# wiring_bord-old.net
KiCad netlist of a schematic drawn in EAGLE
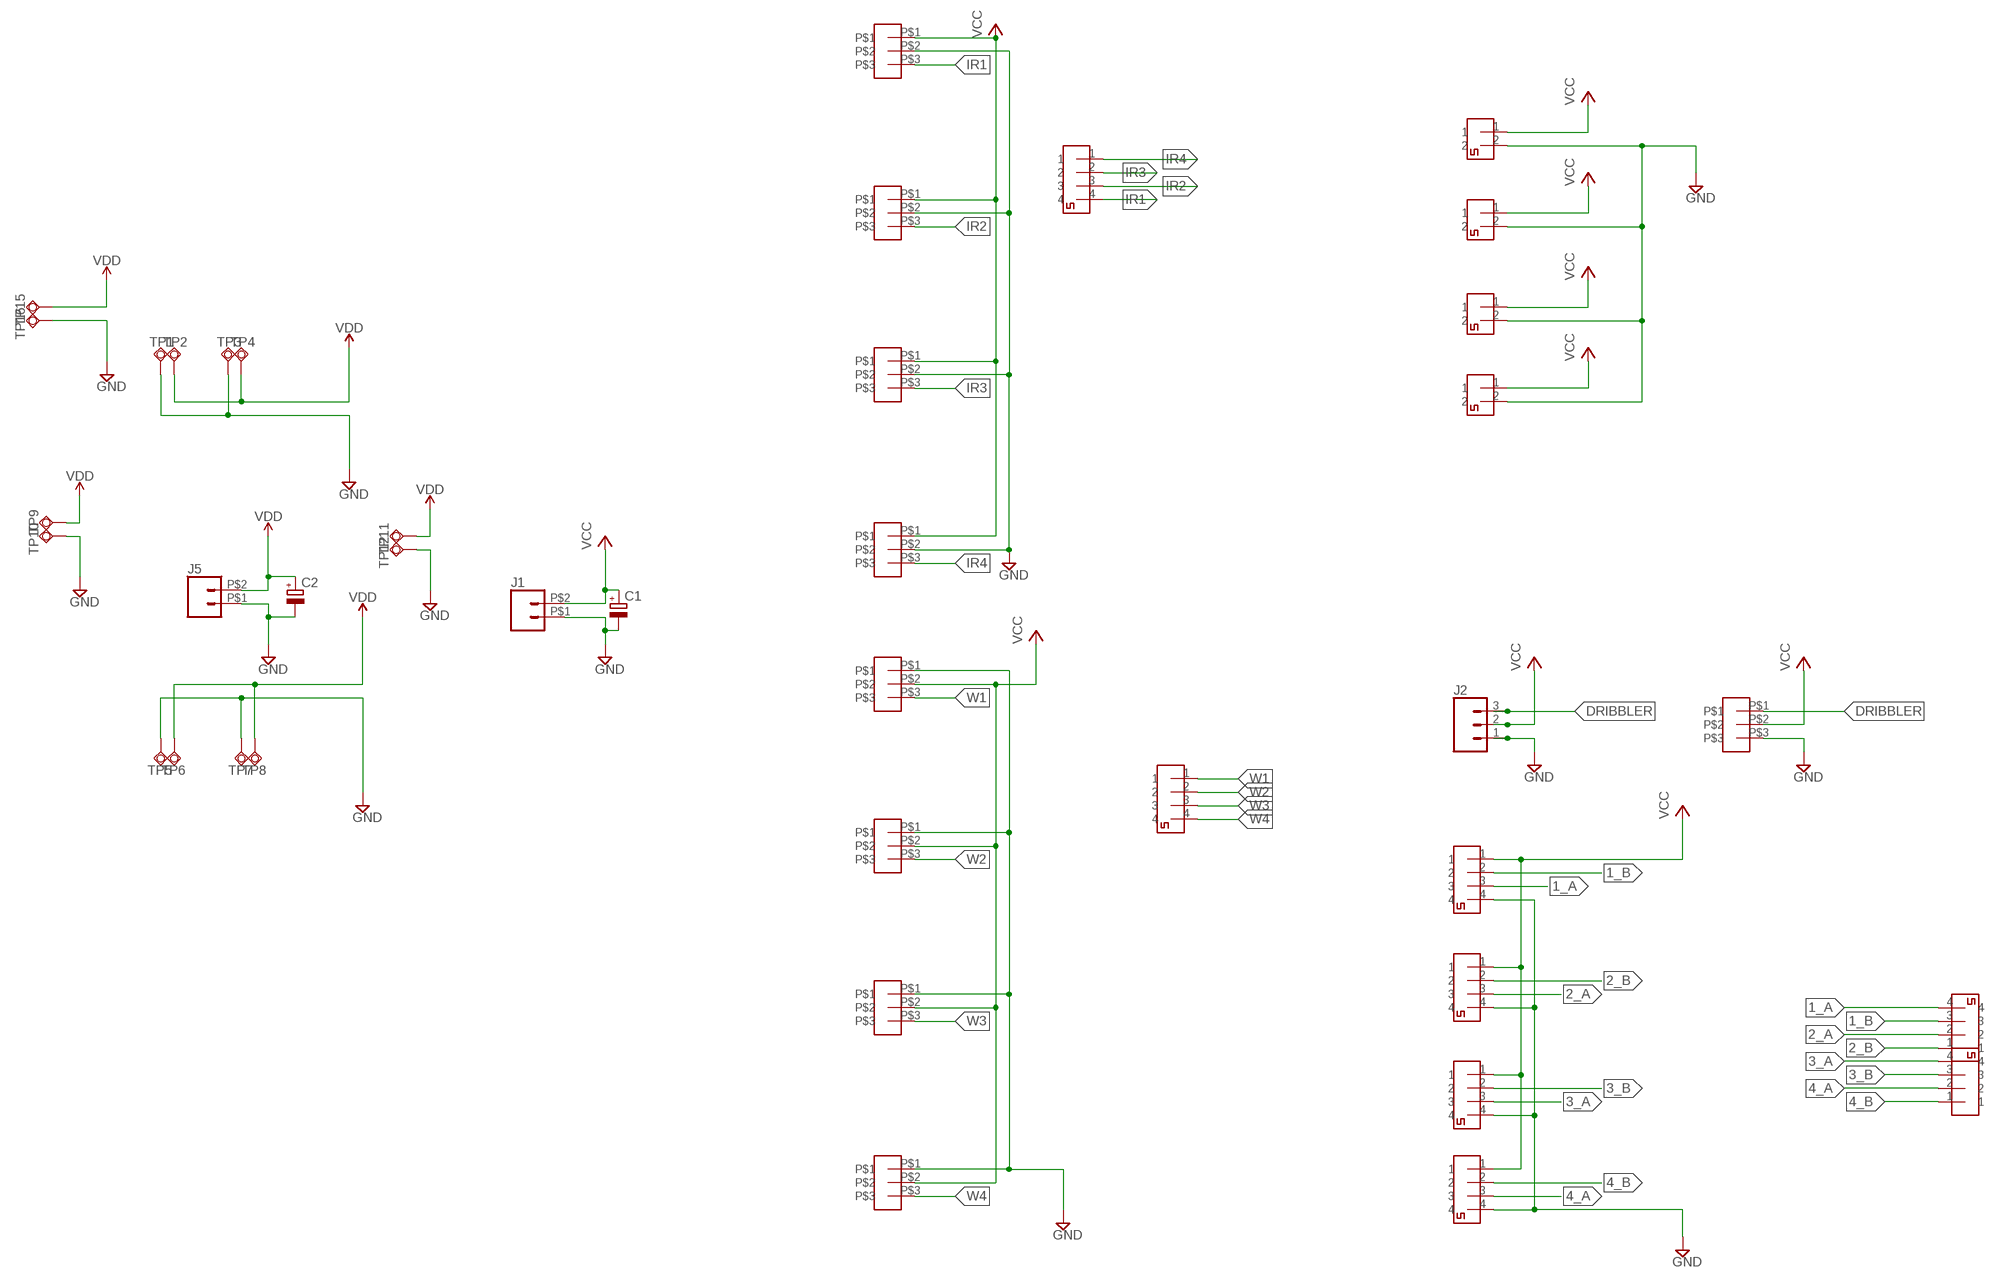
[diagram p0: schematic, sheet 1]

(export (version "E")
  (design (tool "Eeschema 10.0.6"))
  (components
    (comp (ref "C1")
      (value "CPOL-EUE2-5")
      (footprint "eagle-import:E2-5")
      (libsource (lib "eagle-import") (part "CPOL-EUE2-5"))
    )
    (comp (ref "C2")
      (value "CPOL-EUE2-5")
      (footprint "eagle-import:E2-5")
      (libsource (lib "eagle-import") (part "CPOL-EUE2-5"))
    )
    (comp (ref "CONNECTOR1")
      (value "2PIN")
      (footprint "eagle-import:2PIN")
      (libsource (lib "eagle-import") (part "4pin_small_2PIN"))
    )
    (comp (ref "CONNECTOR2")
      (value "2PIN")
      (footprint "eagle-import:2PIN")
      (libsource (lib "eagle-import") (part "4pin_small_2PIN"))
    )
    (comp (ref "CONNECTOR3")
      (value "2PIN")
      (footprint "eagle-import:2PIN")
      (libsource (lib "eagle-import") (part "4pin_small_2PIN"))
    )
    (comp (ref "CONNECTOR4")
      (value "2PIN")
      (footprint "eagle-import:2PIN")
      (libsource (lib "eagle-import") (part "4pin_small_2PIN"))
    )
    (comp (ref "CONNECTOR5")
      (value "2PIN")
      (footprint "eagle-import:2PIN")
      (libsource (lib "eagle-import") (part "2PIN"))
    )
    (comp (ref "CONNECTOR6")
      (value "2PIN")
      (footprint "eagle-import:2PIN")
      (libsource (lib "eagle-import") (part "2PIN"))
    )
    (comp (ref "CONNECTOR7")
      (value "2PIN")
      (footprint "eagle-import:2PIN")
      (libsource (lib "eagle-import") (part "2PIN"))
    )
    (comp (ref "CONNECTOR8")
      (value "2PIN")
      (footprint "eagle-import:2PIN")
      (libsource (lib "eagle-import") (part "2PIN"))
    )
    (comp (ref "ENCODER1")
      (value "2PIN")
      (footprint "eagle-import:2PIN")
      (libsource (lib "eagle-import") (part "4pin_small_2PIN"))
    )
    (comp (ref "ENCODER2")
      (value "2PIN")
      (footprint "eagle-import:2PIN")
      (libsource (lib "eagle-import") (part "4pin_small_2PIN"))
    )
    (comp (ref "ENCODER3")
      (value "2PIN")
      (footprint "eagle-import:2PIN")
      (libsource (lib "eagle-import") (part "4pin_small_2PIN"))
    )
    (comp (ref "ENCODER4")
      (value "2PIN")
      (footprint "eagle-import:2PIN")
      (libsource (lib "eagle-import") (part "4pin_small_2PIN"))
    )
    (comp (ref "IR_DISTANCE1")
      (value "3PIN")
      (footprint "eagle-import:3PIN")
      (libsource (lib "eagle-import") (part "3PIN"))
    )
    (comp (ref "IR_DISTANCE2")
      (value "3PIN")
      (footprint "eagle-import:3PIN")
      (libsource (lib "eagle-import") (part "3PIN"))
    )
    (comp (ref "IR_DISTANCE3")
      (value "3PIN")
      (footprint "eagle-import:3PIN")
      (libsource (lib "eagle-import") (part "3PIN"))
    )
    (comp (ref "IR_DISTANCE4")
      (value "3PIN")
      (footprint "eagle-import:3PIN")
      (libsource (lib "eagle-import") (part "3PIN"))
    )
    (comp (ref "J1")
      (value "CONN_02PTH2")
      (footprint "eagle-import:1X02_BIG")
      (libsource (lib "eagle-import") (part "CONN_02PTH2"))
    )
    (comp (ref "J2")
      (value "CONN_03")
      (footprint "eagle-import:1X03")
      (libsource (lib "eagle-import") (part "CONN_03"))
    )
    (comp (ref "J5")
      (value "CONN_02PTH2")
      (footprint "eagle-import:1X02_BIG")
      (libsource (lib "eagle-import") (part "CONN_02PTH2"))
    )
    (comp (ref "TP1")
      (value "TESTPAD_TPSQPAD1-20")
      (footprint "eagle-import:TESTPAD_P1-20")
      (libsource (lib "eagle-import") (part "TESTPAD_TPSQPAD1-20"))
    )
    (comp (ref "TP2")
      (value "TESTPAD_TPSQPAD1-20")
      (footprint "eagle-import:TESTPAD_P1-20")
      (libsource (lib "eagle-import") (part "TESTPAD_TPSQPAD1-20"))
    )
    (comp (ref "TP3")
      (value "TESTPAD_TPSQPAD1-20")
      (footprint "eagle-import:TESTPAD_P1-20")
      (libsource (lib "eagle-import") (part "TESTPAD_TPSQPAD1-20"))
    )
    (comp (ref "TP4")
      (value "TESTPAD_TPSQPAD1-20")
      (footprint "eagle-import:TESTPAD_P1-20")
      (libsource (lib "eagle-import") (part "TESTPAD_TPSQPAD1-20"))
    )
    (comp (ref "TP5")
      (value "TESTPAD_TPSQPAD1-20")
      (footprint "eagle-import:TESTPAD_P1-20")
      (libsource (lib "eagle-import") (part "TESTPAD_TPSQPAD1-20"))
    )
    (comp (ref "TP6")
      (value "TESTPAD_TPSQPAD1-20")
      (footprint "eagle-import:TESTPAD_P1-20")
      (libsource (lib "eagle-import") (part "TESTPAD_TPSQPAD1-20"))
    )
    (comp (ref "TP7")
      (value "TESTPAD_TPSQPAD1-20")
      (footprint "eagle-import:TESTPAD_P1-20")
      (libsource (lib "eagle-import") (part "TESTPAD_TPSQPAD1-20"))
    )
    (comp (ref "TP8")
      (value "TESTPAD_TPSQPAD1-20")
      (footprint "eagle-import:TESTPAD_P1-20")
      (libsource (lib "eagle-import") (part "TESTPAD_TPSQPAD1-20"))
    )
    (comp (ref "TP9")
      (value "TESTPAD_TPSQPAD1-20")
      (footprint "eagle-import:TESTPAD_P1-20")
      (libsource (lib "eagle-import") (part "TESTPAD_TPSQPAD1-20"))
    )
    (comp (ref "TP10")
      (value "TESTPAD_TPSQPAD1-20")
      (footprint "eagle-import:TESTPAD_P1-20")
      (libsource (lib "eagle-import") (part "TESTPAD_TPSQPAD1-20"))
    )
    (comp (ref "TP11")
      (value "TESTPAD_TPSQPAD1-20")
      (footprint "eagle-import:TESTPAD_P1-20")
      (libsource (lib "eagle-import") (part "TESTPAD_TPSQPAD1-20"))
    )
    (comp (ref "TP12")
      (value "TESTPAD_TPSQPAD1-20")
      (footprint "eagle-import:TESTPAD_P1-20")
      (libsource (lib "eagle-import") (part "TESTPAD_TPSQPAD1-20"))
    )
    (comp (ref "TP15")
      (value "TESTPAD_TPSQPAD1-13")
      (footprint "eagle-import:TESTPAD_P1-13")
      (libsource (lib "eagle-import") (part "TESTPAD_TPSQPAD1-13"))
    )
    (comp (ref "TP16")
      (value "TESTPAD_TPSQPAD1-13")
      (footprint "eagle-import:TESTPAD_P1-13")
      (libsource (lib "eagle-import") (part "TESTPAD_TPSQPAD1-13"))
    )
    (comp (ref "WHITE1")
      (value "3PIN")
      (footprint "eagle-import:3PIN")
      (libsource (lib "eagle-import") (part "3PIN"))
    )
    (comp (ref "WHITE2")
      (value "3PIN")
      (footprint "eagle-import:3PIN")
      (libsource (lib "eagle-import") (part "3PIN"))
    )
    (comp (ref "WHITE3")
      (value "3PIN")
      (footprint "eagle-import:3PIN")
      (libsource (lib "eagle-import") (part "3PIN"))
    )
    (comp (ref "WHITE4")
      (value "3PIN")
      (footprint "eagle-import:3PIN")
      (libsource (lib "eagle-import") (part "3PIN"))
    )
    (comp (ref "WHITE5")
      (value "3PIN")
      (footprint "eagle-import:3PIN")
      (libsource (lib "eagle-import") (part "3PIN"))
    )
  )
  (nets
    (net (code "1") (name "1_A") (class "Default")
      (node (ref "CONNECTOR3") (pin "4") (pinfunction "4_4") (pintype "bidirectional"))
      (node (ref "ENCODER1") (pin "3") (pinfunction "3_3") (pintype "bidirectional"))
    )
    (net (code "2") (name "1_B") (class "Default")
      (node (ref "CONNECTOR3") (pin "3") (pinfunction "3_3") (pintype "bidirectional"))
      (node (ref "ENCODER1") (pin "2") (pinfunction "2_2") (pintype "bidirectional"))
    )
    (net (code "3") (name "2_A") (class "Default")
      (node (ref "CONNECTOR3") (pin "2") (pinfunction "2_2") (pintype "bidirectional"))
      (node (ref "ENCODER2") (pin "3") (pinfunction "3_3") (pintype "bidirectional"))
    )
    (net (code "4") (name "2_B") (class "Default")
      (node (ref "CONNECTOR3") (pin "1") (pinfunction "1_1") (pintype "bidirectional"))
      (node (ref "ENCODER2") (pin "2") (pinfunction "2_2") (pintype "bidirectional"))
    )
    (net (code "5") (name "3_A") (class "Default")
      (node (ref "CONNECTOR4") (pin "4") (pinfunction "4_4") (pintype "bidirectional"))
      (node (ref "ENCODER3") (pin "3") (pinfunction "3_3") (pintype "bidirectional"))
    )
    (net (code "6") (name "3_B") (class "Default")
      (node (ref "CONNECTOR4") (pin "3") (pinfunction "3_3") (pintype "bidirectional"))
      (node (ref "ENCODER3") (pin "2") (pinfunction "2_2") (pintype "bidirectional"))
    )
    (net (code "7") (name "4_A") (class "Default")
      (node (ref "CONNECTOR4") (pin "2") (pinfunction "2_2") (pintype "bidirectional"))
      (node (ref "ENCODER4") (pin "3") (pinfunction "3_3") (pintype "bidirectional"))
    )
    (net (code "8") (name "4_B") (class "Default")
      (node (ref "CONNECTOR4") (pin "1") (pinfunction "1_1") (pintype "bidirectional"))
      (node (ref "ENCODER4") (pin "2") (pinfunction "2_2") (pintype "bidirectional"))
    )
    (net (code "9") (name "DRIBBLER") (class "Default")
      (node (ref "J2") (pin "3") (pinfunction "3_3") (pintype "passive"))
      (node (ref "WHITE5") (pin "P$1") (pinfunction "P$1_P$1") (pintype "bidirectional"))
    )
    (net (code "10") (name "GND") (class "Default")
      (node (ref "C1") (pin "-") (pinfunction "-_-") (pintype "passive"))
      (node (ref "C2") (pin "-") (pinfunction "-_-") (pintype "passive"))
      (node (ref "CONNECTOR5") (pin "2") (pinfunction "2_2") (pintype "bidirectional"))
      (node (ref "CONNECTOR6") (pin "2") (pinfunction "2_2") (pintype "bidirectional"))
      (node (ref "CONNECTOR7") (pin "2") (pinfunction "2_2") (pintype "bidirectional"))
      (node (ref "CONNECTOR8") (pin "2") (pinfunction "2_2") (pintype "bidirectional"))
      (node (ref "ENCODER1") (pin "4") (pinfunction "4_4") (pintype "bidirectional"))
      (node (ref "ENCODER2") (pin "4") (pinfunction "4_4") (pintype "bidirectional"))
      (node (ref "ENCODER3") (pin "4") (pinfunction "4_4") (pintype "bidirectional"))
      (node (ref "ENCODER4") (pin "4") (pinfunction "4_4") (pintype "bidirectional"))
      (node (ref "IR_DISTANCE1") (pin "P$2") (pinfunction "P$2_P$2") (pintype "bidirectional"))
      (node (ref "IR_DISTANCE2") (pin "P$2") (pinfunction "P$2_P$2") (pintype "bidirectional"))
      (node (ref "IR_DISTANCE3") (pin "P$2") (pinfunction "P$2_P$2") (pintype "bidirectional"))
      (node (ref "IR_DISTANCE4") (pin "P$2") (pinfunction "P$2_P$2") (pintype "bidirectional"))
      (node (ref "J1") (pin "P$1") (pinfunction "1_P$1") (pintype "passive"))
      (node (ref "J2") (pin "1") (pinfunction "1_1") (pintype "passive"))
      (node (ref "J5") (pin "P$1") (pinfunction "1_P$1") (pintype "passive"))
      (node (ref "TP1") (pin "TP") (pinfunction "TP_TP") (pintype "input"))
      (node (ref "TP10") (pin "TP") (pinfunction "TP_TP") (pintype "input"))
      (node (ref "TP12") (pin "TP") (pinfunction "TP_TP") (pintype "input"))
      (node (ref "TP16") (pin "TP") (pinfunction "TP_TP") (pintype "input"))
      (node (ref "TP3") (pin "TP") (pinfunction "TP_TP") (pintype "input"))
      (node (ref "TP5") (pin "TP") (pinfunction "TP_TP") (pintype "input"))
      (node (ref "TP7") (pin "TP") (pinfunction "TP_TP") (pintype "input"))
      (node (ref "WHITE1") (pin "P$1") (pinfunction "P$1_P$1") (pintype "bidirectional"))
      (node (ref "WHITE2") (pin "P$1") (pinfunction "P$1_P$1") (pintype "bidirectional"))
      (node (ref "WHITE3") (pin "P$1") (pinfunction "P$1_P$1") (pintype "bidirectional"))
      (node (ref "WHITE4") (pin "P$1") (pinfunction "P$1_P$1") (pintype "bidirectional"))
      (node (ref "WHITE5") (pin "P$3") (pinfunction "P$3_P$3") (pintype "bidirectional"))
    )
    (net (code "11") (name "IR1") (class "Default")
      (node (ref "CONNECTOR1") (pin "4") (pinfunction "4_4") (pintype "bidirectional"))
      (node (ref "IR_DISTANCE1") (pin "P$3") (pinfunction "P$3_P$3") (pintype "bidirectional"))
    )
    (net (code "12") (name "IR2") (class "Default")
      (node (ref "CONNECTOR1") (pin "3") (pinfunction "3_3") (pintype "bidirectional"))
      (node (ref "IR_DISTANCE2") (pin "P$3") (pinfunction "P$3_P$3") (pintype "bidirectional"))
    )
    (net (code "13") (name "IR3") (class "Default")
      (node (ref "CONNECTOR1") (pin "2") (pinfunction "2_2") (pintype "bidirectional"))
      (node (ref "IR_DISTANCE3") (pin "P$3") (pinfunction "P$3_P$3") (pintype "bidirectional"))
    )
    (net (code "14") (name "IR4") (class "Default")
      (node (ref "CONNECTOR1") (pin "1") (pinfunction "1_1") (pintype "bidirectional"))
      (node (ref "IR_DISTANCE4") (pin "P$3") (pinfunction "P$3_P$3") (pintype "bidirectional"))
    )
    (net (code "15") (name "VCC") (class "Default")
      (node (ref "C1") (pin "+") (pinfunction "+_+") (pintype "passive"))
      (node (ref "CONNECTOR5") (pin "1") (pinfunction "1_1") (pintype "bidirectional"))
      (node (ref "CONNECTOR6") (pin "1") (pinfunction "1_1") (pintype "bidirectional"))
      (node (ref "CONNECTOR7") (pin "1") (pinfunction "1_1") (pintype "bidirectional"))
      (node (ref "CONNECTOR8") (pin "1") (pinfunction "1_1") (pintype "bidirectional"))
      (node (ref "ENCODER1") (pin "1") (pinfunction "1_1") (pintype "bidirectional"))
      (node (ref "ENCODER2") (pin "1") (pinfunction "1_1") (pintype "bidirectional"))
      (node (ref "ENCODER3") (pin "1") (pinfunction "1_1") (pintype "bidirectional"))
      (node (ref "ENCODER4") (pin "1") (pinfunction "1_1") (pintype "bidirectional"))
      (node (ref "IR_DISTANCE1") (pin "P$1") (pinfunction "P$1_P$1") (pintype "bidirectional"))
      (node (ref "IR_DISTANCE2") (pin "P$1") (pinfunction "P$1_P$1") (pintype "bidirectional"))
      (node (ref "IR_DISTANCE3") (pin "P$1") (pinfunction "P$1_P$1") (pintype "bidirectional"))
      (node (ref "IR_DISTANCE4") (pin "P$1") (pinfunction "P$1_P$1") (pintype "bidirectional"))
      (node (ref "J1") (pin "P$2") (pinfunction "2_P$2") (pintype "passive"))
      (node (ref "J2") (pin "2") (pinfunction "2_2") (pintype "passive"))
      (node (ref "WHITE1") (pin "P$2") (pinfunction "P$2_P$2") (pintype "bidirectional"))
      (node (ref "WHITE2") (pin "P$2") (pinfunction "P$2_P$2") (pintype "bidirectional"))
      (node (ref "WHITE3") (pin "P$2") (pinfunction "P$2_P$2") (pintype "bidirectional"))
      (node (ref "WHITE4") (pin "P$2") (pinfunction "P$2_P$2") (pintype "bidirectional"))
      (node (ref "WHITE5") (pin "P$2") (pinfunction "P$2_P$2") (pintype "bidirectional"))
    )
    (net (code "16") (name "VDD") (class "Default")
      (node (ref "C2") (pin "+") (pinfunction "+_+") (pintype "passive"))
      (node (ref "J5") (pin "P$2") (pinfunction "2_P$2") (pintype "passive"))
      (node (ref "TP11") (pin "TP") (pinfunction "TP_TP") (pintype "input"))
      (node (ref "TP15") (pin "TP") (pinfunction "TP_TP") (pintype "input"))
      (node (ref "TP2") (pin "TP") (pinfunction "TP_TP") (pintype "input"))
      (node (ref "TP4") (pin "TP") (pinfunction "TP_TP") (pintype "input"))
      (node (ref "TP6") (pin "TP") (pinfunction "TP_TP") (pintype "input"))
      (node (ref "TP8") (pin "TP") (pinfunction "TP_TP") (pintype "input"))
      (node (ref "TP9") (pin "TP") (pinfunction "TP_TP") (pintype "input"))
    )
    (net (code "17") (name "W1") (class "Default")
      (node (ref "CONNECTOR2") (pin "1") (pinfunction "1_1") (pintype "bidirectional"))
      (node (ref "WHITE1") (pin "P$3") (pinfunction "P$3_P$3") (pintype "bidirectional"))
    )
    (net (code "18") (name "W2") (class "Default")
      (node (ref "CONNECTOR2") (pin "2") (pinfunction "2_2") (pintype "bidirectional"))
      (node (ref "WHITE2") (pin "P$3") (pinfunction "P$3_P$3") (pintype "bidirectional"))
    )
    (net (code "19") (name "W3") (class "Default")
      (node (ref "CONNECTOR2") (pin "3") (pinfunction "3_3") (pintype "bidirectional"))
      (node (ref "WHITE3") (pin "P$3") (pinfunction "P$3_P$3") (pintype "bidirectional"))
    )
    (net (code "20") (name "W4") (class "Default")
      (node (ref "CONNECTOR2") (pin "4") (pinfunction "4_4") (pintype "bidirectional"))
      (node (ref "WHITE4") (pin "P$3") (pinfunction "P$3_P$3") (pintype "bidirectional"))
    )
  )
)
